# 03_CONNECTORS_AUDIO_CONTROL_INPUTS.net
KiCad netlist of a schematic drawn in Altium Designer
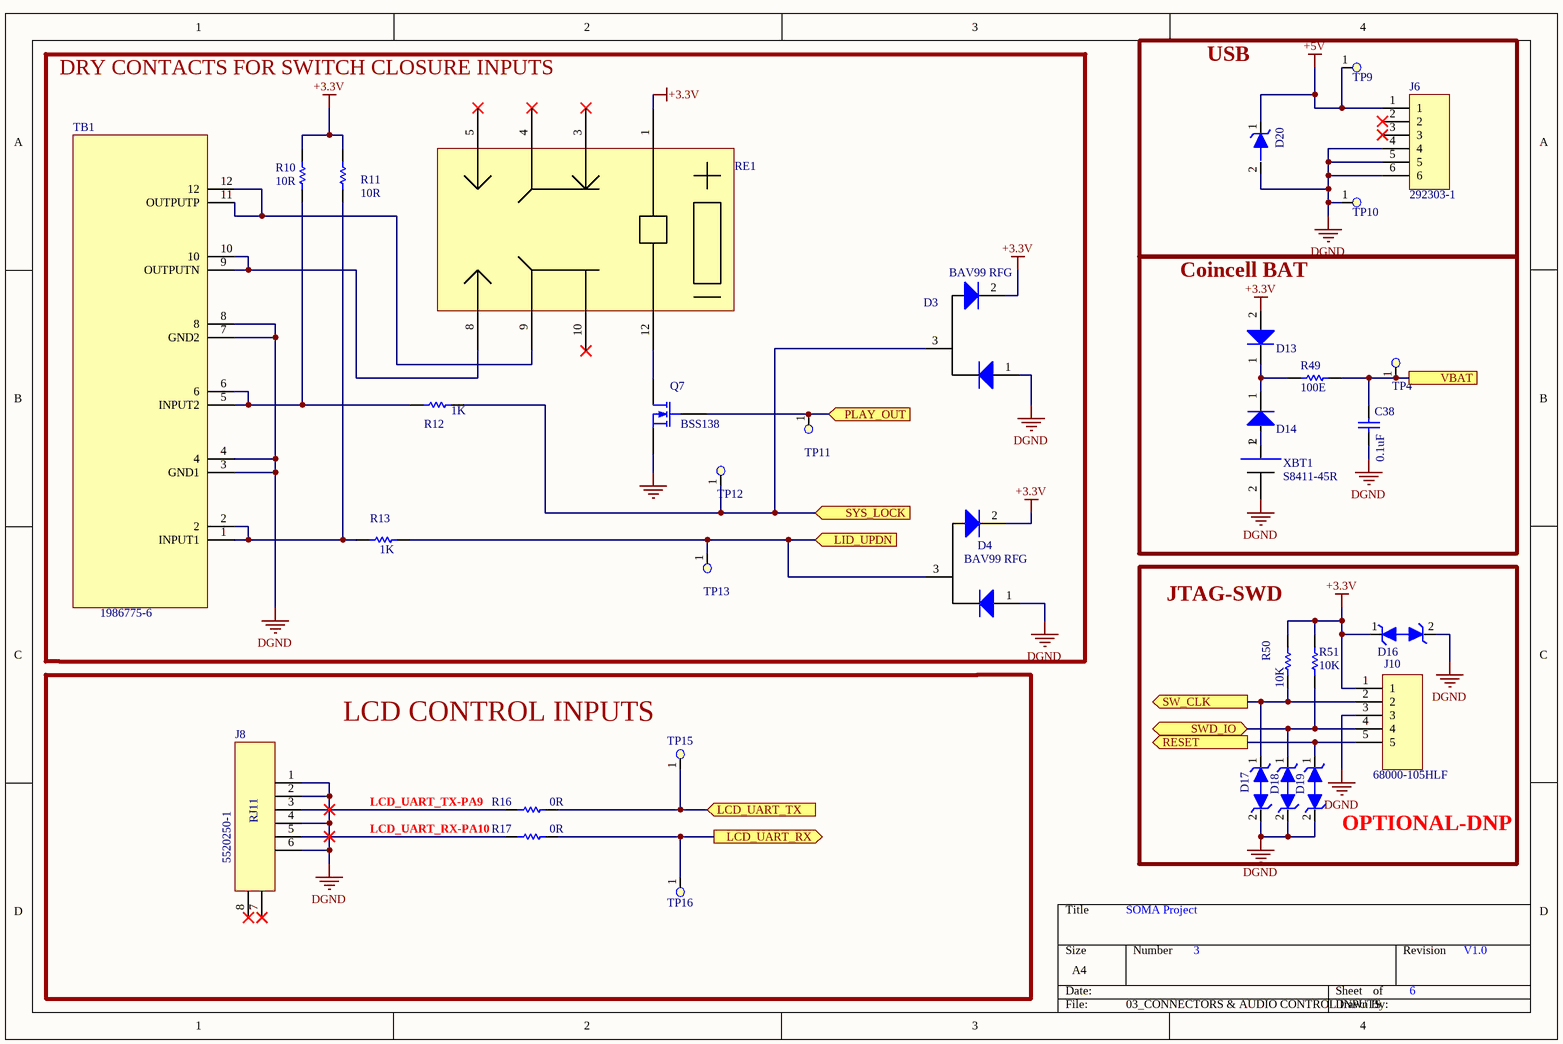
[diagram p0: 03_CONNECTORS & AUDIO CONTROL INPUTS.SchDoc]

(export (version "E")
  (design (tool "Eeschema 10.0.6"))
  (components
    (comp (ref "C38")
      (value "0.1uF")
      (footprint "C0603")
      (description "CAP CER 0.1UF 10V X7R 0603")
      (fields
        (field (name "MANUFACTURER") "Würth Elektronik")
        (field (name "DISTRIBUTOR PART NUMBER") "732-7939-1-ND")
      )
      (libsource (lib "SOMA_1") (part "CAP CER 0.1UF 10V X7R 0603"))
    )
    (comp (ref "D3")
      (value "BAV99 RFG")
      (footprint "SOT95P240X130-3N")
      (description "Diode Array 1 Pair Series Connection Standard 70V 200mA Surface Mount TO-236-3, SC-59, SOT-23-3")
      (fields
        (field (name "MANUFACTURER") "Taiwan Semiconductor Corporation")
        (field (name "DISTRIBUTOR PART NUMBER") "BAV99RFGTR-ND")
      )
      (libsource (lib "SOMA_15072021") (part "DIODE ARRAY GP 70V 200MA SOT23"))
    )
    (comp (ref "D4")
      (value "BAV99 RFG")
      (footprint "SOT95P240X130-3N")
      (description "Diode Array 1 Pair Series Connection Standard 70V 200mA Surface Mount TO-236-3, SC-59, SOT-23-3")
      (fields
        (field (name "MANUFACTURER") "Taiwan Semiconductor Corporation")
        (field (name "DISTRIBUTOR PART NUMBER") "BAV99RFGTR-ND")
      )
      (libsource (lib "SOMA_15072021") (part "DIODE ARRAY GP 70V 200MA SOT23"))
    )
    (comp (ref "D13")
      (value "DIODE SCHOTTKY 30V 200MA SOD123")
      (footprint "SOD3715X140N_2A")
      (fields
        (field (name "MANUFACTURER") "Diodes Incorporated")
        (field (name "MANUFACTURER PART NUMBER") "BAT43W-7-F")
        (field (name "DISTRIBUTOR PART NUMBER") "BAT43W-FDICT-ND")
      )
      (libsource (lib "SOMA_15072021") (part "DIODE SCHOTTKY 30V 200MA SOD123"))
    )
    (comp (ref "D14")
      (value "DIODE SCHOTTKY 30V 200MA SOD123")
      (footprint "SOD3715X140N_2A")
      (fields
        (field (name "MANUFACTURER") "Diodes Incorporated")
        (field (name "MANUFACTURER PART NUMBER") "BAT43W-7-F")
        (field (name "DISTRIBUTOR PART NUMBER") "BAT43W-FDICT-ND")
      )
      (libsource (lib "SOMA_15072021") (part "DIODE SCHOTTKY 30V 200MA SOD123"))
    )
    (comp (ref "D16")
      (value "TVS DIODE 3.3VWM 11.5VC SOD923")
      (footprint "SOD1006X40N_BI")
      (description "11.5V Clamp 2A (8/20µs) Ipp Tvs Diode Surface Mount SOD-923")
      (fields
        (field (name "MANUFACTURER PART NUMBER") "ESD9B3.3ST5G")
        (field (name "MANUFACTURER") "ON Semiconductor")
      )
      (libsource (lib "SOMA_15072021") (part "TVS DIODE 3.3VWM 11.5VC SOD923"))
    )
    (comp (ref "D17")
      (value "TVS DIODE 3.3VWM 11.5VC SOD923")
      (footprint "SOD1006X40N_BI")
      (description "11.5V Clamp 2A (8/20µs) Ipp Tvs Diode Surface Mount SOD-923")
      (fields
        (field (name "MANUFACTURER PART NUMBER") "ESD9B3.3ST5G")
        (field (name "MANUFACTURER") "ON Semiconductor")
      )
      (libsource (lib "SOMA_15072021") (part "TVS DIODE 3.3VWM 11.5VC SOD923"))
    )
    (comp (ref "D18")
      (value "TVS DIODE 3.3VWM 11.5VC SOD923")
      (footprint "SOD1006X40N_BI")
      (description "11.5V Clamp 2A (8/20µs) Ipp Tvs Diode Surface Mount SOD-923")
      (fields
        (field (name "MANUFACTURER PART NUMBER") "ESD9B3.3ST5G")
        (field (name "MANUFACTURER") "ON Semiconductor")
      )
      (libsource (lib "SOMA_15072021") (part "TVS DIODE 3.3VWM 11.5VC SOD923"))
    )
    (comp (ref "D19")
      (value "TVS DIODE 3.3VWM 11.5VC SOD923")
      (footprint "SOD1006X40N_BI")
      (description "11.5V Clamp 2A (8/20µs) Ipp Tvs Diode Surface Mount SOD-923")
      (fields
        (field (name "MANUFACTURER PART NUMBER") "ESD9B3.3ST5G")
        (field (name "MANUFACTURER") "ON Semiconductor")
      )
      (libsource (lib "SOMA_15072021") (part "TVS DIODE 3.3VWM 11.5VC SOD923"))
    )
    (comp (ref "D20")
      (value "TVS DIODE 5VWM 12VC SOD723")
      (footprint "SOD1460X65N_2A")
      (fields
        (field (name "MANUFACTURER PART NUMBER") "SP1003-01DTG")
        (field (name "MANUFACTURER") "Littelfuse Inc.")
        (field (name "DISTRIBUTOR PART NUMBER") "576-SP1003-01DTG")
      )
      (libsource (lib "SOMA_15072021") (part "SP1003-01DTG"))
    )
    (comp (ref "J6")
      (value "292303-1")
      (footprint "TE_292303-1")
      (description "CONN RCPT USB2.0 TYPEA 4POS R/A")
      (fields
        (field (name "DISTRIBUTOR PART NUMBER") "A31726-ND")
        (field (name "MANUFACTURER") "TE Connectivity AMP Connectors")
      )
      (libsource (lib "SOMA_15072021") (part "CONN RCPT USB2.0 TYPEA 4POS R/A"))
    )
    (comp (ref "J8")
      (value "CONN MOD JACK 6P2C R/A UNSHLD")
      (footprint "TE_5520250-1")
      (description "Jack Modular Connector 6p2c (RJ11) 90° Angle (Right) Unshielded Cat3")
      (fields
        (field (name "MANUFACTURER") "TE Connectivity AMP Connectors")
        (field (name "DISTRIBUTOR PART NUMBER") "A31404-ND")
        (field (name "MANUFACTURER PART NUMBER") "5520250-1")
      )
      (libsource (lib "SOMA_15072021") (part "CONN MOD JACK 6P2C R/A UNSHLD"))
    )
    (comp (ref "J10")
      (value "68000-105HLF")
      (footprint "BERG_1X5")
      (description "CONN HEADER VERT 5POS 2.54MM")
      (fields
        (field (name "DISTRIBUTOR PART NUMBER") "609-3462-ND")
        (field (name "MANUFACTURER") "Amphenol ICC (FCI)")
      )
      (libsource (lib "SOMA_15072021") (part "CONN HEADER VERT 5POS 2.54MM"))
    )
    (comp (ref "Q7")
      (value "BSS138")
      (footprint "SOT95P240X110-3N")
      (description "N-Channel 50V 220mA (Ta) 360mW (Ta) Surface Mount SOT-23-3")
      (fields
        (field (name "DISTRIBUTOR PART NUMBER") "BSS138CT-ND")
        (field (name "MANUFACTURER") "ON Semiconductor")
      )
      (libsource (lib "SOMA_15072021") (part "MOSFET N-CH 50V 220MA SOT23-3"))
    )
    (comp (ref "R10")
      (value "10R")
      (footprint "R0402")
      (description "10 Ohms ±5% 0.063W, 1/16W Chip Resistor 0402 (1005 Metric) Automotive AEC-Q200 Thick Film")
      (fields (field (name "TOLERANCE") "±5%") (field (name "MANUFACTURER") "Vishay Dale"))
      (libsource (lib "SOMA_15072021") (part "RES SMD 10 OHM 5% 1/16W 0402"))
    )
    (comp (ref "R11")
      (value "10R")
      (footprint "R0402")
      (description "10 Ohms ±5% 0.063W, 1/16W Chip Resistor 0402 (1005 Metric) Automotive AEC-Q200 Thick Film")
      (fields (field (name "TOLERANCE") "±5%") (field (name "MANUFACTURER") "Vishay Dale"))
      (libsource (lib "SOMA_15072021") (part "RES SMD 10 OHM 5% 1/16W 0402"))
    )
    (comp (ref "R12")
      (value "1K")
      (footprint "R0402")
      (description "RES SMD 1K OHM 1% 1/16W 0402")
      (fields (field (name "TOLERANCE") "±1%") (field (name "MANUFACTURER") "Yageo"))
      (libsource (lib "SOMA_15072021") (part "RES SMD 1K OHM 1% 1/16W 0402"))
    )
    (comp (ref "R13")
      (value "1K")
      (footprint "R0402")
      (description "RES SMD 1K OHM 1% 1/16W 0402")
      (fields (field (name "TOLERANCE") "±1%") (field (name "MANUFACTURER") "Yageo"))
      (libsource (lib "SOMA_15072021") (part "RES SMD 1K OHM 1% 1/16W 0402"))
    )
    (comp (ref "R16")
      (value "0R")
      (footprint "R0402")
      (description "0 Ohms Jumper 0.063W, 1/16W Chip Resistor 0402 (1005 Metric) Moisture Resistant Thick Film")
      (fields (field (name "MANUFACTURER") "Yageo") (field (name "DISTRIBUTOR PART NUMBER") "YAG1279TR-ND"))
      (libsource (lib "SOMA_1") (part "RES SMD 0 OHM JUMPER 1/16W 0402"))
    )
    (comp (ref "R17")
      (value "0R")
      (footprint "R0402")
      (description "0 Ohms Jumper 0.063W, 1/16W Chip Resistor 0402 (1005 Metric) Moisture Resistant Thick Film")
      (fields (field (name "MANUFACTURER") "Yageo") (field (name "DISTRIBUTOR PART NUMBER") "YAG1279TR-ND"))
      (libsource (lib "SOMA_1") (part "RES SMD 0 OHM JUMPER 1/16W 0402"))
    )
    (comp (ref "R49")
      (value "100E")
      (footprint "R0402")
      (description "100 Ohms ±1% 0.1W, 1/10W Chip Resistor 0402 (1005 Metric) Automotive AEC-Q200 Thick Film")
      (fields
        (field (name "MANUFACTURER") "Panasonic Electronic Components")
        (field (name "MANUFACTURER PART NUMBER") "ERJ-2RKF1000X")
      )
      (libsource (lib "SOMA_15072021") (part "RES SMD 100 OHM 1% 1/10W 0402"))
    )
    (comp (ref "R50")
      (value "10K")
      (footprint "R0402")
      (description "10 kOhms ±1% 0.1W, 1/10W Chip Resistor 0402 (1005 Metric) Automotive AEC-Q200 Thick Film")
      (fields
        (field (name "MANUFACTURER") "Panasonic Electronic Components")
        (field (name "DISTRIBUTOR PART NUMBER") "P10.0KLCT-ND")
      )
      (libsource (lib "Daughtercard_Library") (part "RES SMD 10K OHM 1% 1/10W 0402"))
    )
    (comp (ref "R51")
      (value "10K")
      (footprint "R0402")
      (description "10 kOhms ±1% 0.1W, 1/10W Chip Resistor 0402 (1005 Metric) Automotive AEC-Q200 Thick Film")
      (fields
        (field (name "MANUFACTURER") "Panasonic Electronic Components")
        (field (name "DISTRIBUTOR PART NUMBER") "P10.0KLCT-ND")
      )
      (libsource (lib "Daughtercard_Library") (part "RES SMD 10K OHM 1% 1/10W 0402"))
    )
    (comp (ref "RE1")
      (value "RELAY GEN PURPOSE DPDT 1A 3VDC")
      (footprint "RELAY_TXS2SA-3V")
      (description "General Purpose Relay DPDT (2 Form C) Surface Mount")
      (fields
        (field (name "DISTRIBUTOR PART NUMBER") "255-2341-5-ND")
        (field (name "MANUFACTURER") "Panasonic Electric Works")
      )
      (libsource (lib "SOMA_15072021") (part "RELAY GEN PURPOSE DPDT 1A 3VDC"))
    )
    (comp (ref "TB1")
      (value "TERM BLK 6P SIDE ENT 5.08MM PCB")
      (footprint "TE_1986775-6")
      (description "6 Position Wire to Board Terminal Block Horizontal with Board 0.200\" (5.08mm) Through Hole")
      (fields
        (field (name "MANUFACTURER") "TE Connectivity AMP Connectors")
        (field (name "MANUFACTURER PART NUMBER") "1986775-6")
        (field (name "DISTRIBUTOR PART NUMBER") "A120496-ND")
      )
      (libsource (lib "SOMA_15072021") (part "TERM BLK 6P SIDE ENT 5.08MM PCB"))
    )
    (comp (ref "TP4")
      (value "Test Point,1.6mm Diameter,SMD")
      (footprint "TP_63C")
      (libsource (lib "SOMA_1") (part "Test Point,1.6mm Diameter,SMD"))
    )
    (comp (ref "TP9")
      (value "Test Point,1.6mm Diameter,SMD")
      (footprint "TP_63C")
      (libsource (lib "SOMA_1") (part "Test Point,1.6mm Diameter,SMD"))
    )
    (comp (ref "TP10")
      (value "Test Point,1.6mm Diameter,SMD")
      (footprint "TP_63C")
      (libsource (lib "SOMA_1") (part "Test Point,1.6mm Diameter,SMD"))
    )
    (comp (ref "TP11")
      (value "Test Point,1.6mm Diameter,SMD")
      (footprint "TP_63C")
      (libsource (lib "SOMA_1") (part "Test Point,1.6mm Diameter,SMD"))
    )
    (comp (ref "TP12")
      (value "Test Point,1.6mm Diameter,SMD")
      (footprint "TP_63C")
      (libsource (lib "SOMA_1") (part "Test Point,1.6mm Diameter,SMD"))
    )
    (comp (ref "TP13")
      (value "Test Point,1.6mm Diameter,SMD")
      (footprint "TP_63C")
      (libsource (lib "SOMA_1") (part "Test Point,1.6mm Diameter,SMD"))
    )
    (comp (ref "TP15")
      (value "Test Point,1.6mm Diameter,SMD")
      (footprint "TP_63C")
      (libsource (lib "SOMA_1") (part "Test Point,1.6mm Diameter,SMD"))
    )
    (comp (ref "TP16")
      (value "Test Point,1.6mm Diameter,SMD")
      (footprint "TP_63C")
      (libsource (lib "SOMA_1") (part "Test Point,1.6mm Diameter,SMD"))
    )
    (comp (ref "XBT1")
      (value "BATTERY HOLDER COIN 12MM SMD")
      (footprint "HLDR_S8411-45R")
      (fields
        (field (name "MANUFACTURER") "Harwin Inc.")
        (field (name "DISTRIBUTOR PART NUMBER") "952-1745-1-ND")
        (field (name "MANUFACTURER PART NUMBER") "S8411-45R")
      )
      (libsource (lib "SOMA_15072021") (part "BATTERY HOLDER COIN 12MM SMD"))
    )
  )
  (nets
    (net (code "1") (name "+3.3V") (class "Default")
      (node (ref "D13") (pin "2") (pinfunction "A_2") (pintype "passive"))
      (node (ref "D16") (pin "1") (pinfunction "K_1") (pintype "passive"))
      (node (ref "D3") (pin "2") (pinfunction "K_2") (pintype "passive"))
      (node (ref "D4") (pin "2") (pinfunction "K_2") (pintype "passive"))
      (node (ref "J10") (pin "1") (pinfunction "1_1") (pintype "passive"))
      (node (ref "R10") (pin "2") (pinfunction "2_2") (pintype "passive"))
      (node (ref "R11") (pin "2") (pinfunction "2_2") (pintype "passive"))
      (node (ref "R50") (pin "2") (pinfunction "2_2") (pintype "passive"))
      (node (ref "R51") (pin "2") (pinfunction "2_2") (pintype "passive"))
      (node (ref "RE1") (pin "1") (pinfunction "1_1") (pintype "passive"))
    )
    (net (code "2") (name "+5V") (class "Default")
      (node (ref "D20") (pin "1") (pinfunction "K_1") (pintype "passive"))
      (node (ref "J6") (pin "1") (pinfunction "1_1") (pintype "passive"))
      (node (ref "TP9") (pin "1") (pinfunction "0_1") (pintype "passive"))
    )
    (net (code "3") (name "/LCD_UART_RX") (class "Default")
      (node (ref "R17") (pin "2") (pinfunction "2_2") (pintype "passive"))
      (node (ref "TP16") (pin "1") (pinfunction "0_1") (pintype "passive"))
    )
    (net (code "4") (name "/LCD_UART_RX-PA10") (class "Default")
      (node (ref "J8") (pin "5") (pinfunction "5_5") (pintype "passive"))
      (node (ref "R17") (pin "1") (pinfunction "1_1") (pintype "passive"))
    )
    (net (code "5") (name "/LCD_UART_TX") (class "Default")
      (node (ref "R16") (pin "2") (pinfunction "2_2") (pintype "passive"))
      (node (ref "TP15") (pin "1") (pinfunction "0_1") (pintype "passive"))
    )
    (net (code "6") (name "/LCD_UART_TX-PA9") (class "Default")
      (node (ref "J8") (pin "3") (pinfunction "3_3") (pintype "passive"))
      (node (ref "R16") (pin "1") (pinfunction "1_1") (pintype "passive"))
    )
    (net (code "7") (name "/LID_UPDN") (class "Default")
      (node (ref "D4") (pin "3") (pinfunction "AK_3") (pintype "passive"))
      (node (ref "R13") (pin "2") (pinfunction "2_2") (pintype "passive"))
      (node (ref "TP13") (pin "1") (pinfunction "0_1") (pintype "passive"))
    )
    (net (code "8") (name "/PLAY_OUT") (class "Default")
      (node (ref "Q7") (pin "1") (pinfunction "G_1") (pintype "passive"))
      (node (ref "TP11") (pin "1") (pinfunction "0_1") (pintype "passive"))
    )
    (net (code "9") (name "/RESET") (class "Default")
      (node (ref "D19") (pin "1") (pinfunction "K_1") (pintype "passive"))
      (node (ref "J10") (pin "5") (pinfunction "5_5") (pintype "passive"))
    )
    (net (code "10") (name "/SWD_IO") (class "Default")
      (node (ref "D18") (pin "1") (pinfunction "K_1") (pintype "passive"))
      (node (ref "J10") (pin "4") (pinfunction "4_4") (pintype "passive"))
      (node (ref "R51") (pin "1") (pinfunction "1_1") (pintype "passive"))
    )
    (net (code "11") (name "/SW_CLK") (class "Default")
      (node (ref "D17") (pin "1") (pinfunction "K_1") (pintype "passive"))
      (node (ref "J10") (pin "2") (pinfunction "2_2") (pintype "passive"))
      (node (ref "R50") (pin "1") (pinfunction "1_1") (pintype "passive"))
    )
    (net (code "12") (name "/SYS_LOCK") (class "Default")
      (node (ref "D3") (pin "3") (pinfunction "AK_3") (pintype "passive"))
      (node (ref "R12") (pin "2") (pinfunction "2_2") (pintype "passive"))
      (node (ref "TP12") (pin "1") (pinfunction "0_1") (pintype "passive"))
    )
    (net (code "13") (name "/VBAT") (class "Default")
      (node (ref "C38") (pin "2") (pinfunction "2_2") (pintype "passive"))
      (node (ref "R49") (pin "2") (pinfunction "2_2") (pintype "passive"))
      (node (ref "TP4") (pin "1") (pinfunction "0_1") (pintype "passive"))
    )
    (net (code "14") (name "DGND") (class "Default")
      (node (ref "C38") (pin "1") (pinfunction "1_1") (pintype "passive"))
      (node (ref "D16") (pin "2") (pinfunction "A_2") (pintype "passive"))
      (node (ref "D17") (pin "2") (pinfunction "A_2") (pintype "passive"))
      (node (ref "D18") (pin "2") (pinfunction "A_2") (pintype "passive"))
      (node (ref "D19") (pin "2") (pinfunction "A_2") (pintype "passive"))
      (node (ref "D20") (pin "2") (pinfunction "A_2") (pintype "passive"))
      (node (ref "D3") (pin "1") (pinfunction "A_1") (pintype "passive"))
      (node (ref "D4") (pin "1") (pinfunction "A_1") (pintype "passive"))
      (node (ref "J10") (pin "3") (pinfunction "3_3") (pintype "passive"))
      (node (ref "J6") (pin "4") (pinfunction "4_4") (pintype "passive"))
      (node (ref "J6") (pin "5") (pinfunction "5_5") (pintype "passive"))
      (node (ref "J6") (pin "6") (pinfunction "6_6") (pintype "passive"))
      (node (ref "J8") (pin "1") (pinfunction "1_1") (pintype "passive"))
      (node (ref "J8") (pin "2") (pinfunction "2_2") (pintype "passive"))
      (node (ref "J8") (pin "4") (pinfunction "4_4") (pintype "passive"))
      (node (ref "J8") (pin "6") (pinfunction "6_6") (pintype "passive"))
      (node (ref "TB1") (pin "3") (pinfunction "GND1_3") (pintype "passive"))
      (node (ref "TB1") (pin "4") (pinfunction "4_4") (pintype "passive"))
      (node (ref "TB1") (pin "7") (pinfunction "GND2_7") (pintype "passive"))
      (node (ref "TB1") (pin "8") (pinfunction "8_8") (pintype "passive"))
      (node (ref "TP10") (pin "1") (pinfunction "0_1") (pintype "passive"))
      (node (ref "XBT1") (pin "2") (pinfunction "-_2") (pintype "passive"))
    )
    (net (code "15") (name "GND") (class "Default")
      (node (ref "Q7") (pin "2") (pinfunction "S_2") (pintype "passive"))
    )
    (net (code "16") (name "Net-(D13-K)") (class "Default")
      (node (ref "D13") (pin "1") (pinfunction "K_1") (pintype "passive"))
      (node (ref "D14") (pin "1") (pinfunction "K_1") (pintype "passive"))
      (node (ref "R49") (pin "1") (pinfunction "1_1") (pintype "passive"))
    )
    (net (code "17") (name "Net-(D14-A)") (class "Default")
      (node (ref "D14") (pin "2") (pinfunction "A_2") (pintype "passive"))
      (node (ref "XBT1") (pin "1") (pinfunction "+_1") (pintype "passive"))
    )
    (net (code "18") (name "Net-(Q7-D)") (class "Default")
      (node (ref "Q7") (pin "3") (pinfunction "D_3") (pintype "passive"))
      (node (ref "RE1") (pin "12") (pinfunction "12_12") (pintype "passive"))
    )
    (net (code "19") (name "Net-(TB1-INPUT1)") (class "Default")
      (node (ref "R11") (pin "1") (pinfunction "1_1") (pintype "passive"))
      (node (ref "R13") (pin "1") (pinfunction "1_1") (pintype "passive"))
      (node (ref "TB1") (pin "1") (pinfunction "INPUT1_1") (pintype "passive"))
      (node (ref "TB1") (pin "2") (pinfunction "2_2") (pintype "passive"))
    )
    (net (code "20") (name "Net-(TB1-INPUT2)") (class "Default")
      (node (ref "R10") (pin "1") (pinfunction "1_1") (pintype "passive"))
      (node (ref "R12") (pin "1") (pinfunction "1_1") (pintype "passive"))
      (node (ref "TB1") (pin "5") (pinfunction "INPUT2_5") (pintype "passive"))
      (node (ref "TB1") (pin "6") (pinfunction "6_6") (pintype "passive"))
    )
    (net (code "21") (name "Net-(TB1-OUTPUTN)") (class "Default")
      (node (ref "RE1") (pin "8") (pinfunction "8_8") (pintype "passive"))
      (node (ref "TB1") (pin "10") (pinfunction "10_10") (pintype "passive"))
      (node (ref "TB1") (pin "9") (pinfunction "OUTPUTN_9") (pintype "passive"))
    )
    (net (code "22") (name "Net-(TB1-OUTPUTP)") (class "Default")
      (node (ref "RE1") (pin "9") (pinfunction "9_9") (pintype "passive"))
      (node (ref "TB1") (pin "11") (pinfunction "OUTPUTP_11") (pintype "passive"))
      (node (ref "TB1") (pin "12") (pinfunction "12_12") (pintype "passive"))
    )
    (net (code "23") (name "unconnected-(J6-Pad2)") (class "Default")
      (node (ref "J6") (pin "2") (pinfunction "2_2") (pintype "passive+no_connect"))
    )
    (net (code "24") (name "unconnected-(J6-Pad3)") (class "Default")
      (node (ref "J6") (pin "3") (pinfunction "3_3") (pintype "passive+no_connect"))
    )
    (net (code "25") (name "unconnected-(J8-Pad7)") (class "Default")
      (node (ref "J8") (pin "7") (pinfunction "7_7") (pintype "passive+no_connect"))
    )
    (net (code "26") (name "unconnected-(J8-Pad8)") (class "Default")
      (node (ref "J8") (pin "8") (pinfunction "8_8") (pintype "passive+no_connect"))
    )
    (net (code "27") (name "unconnected-(RE1-Pad3)") (class "Default")
      (node (ref "RE1") (pin "3") (pinfunction "3_3") (pintype "passive+no_connect"))
    )
    (net (code "28") (name "unconnected-(RE1-Pad4)") (class "Default")
      (node (ref "RE1") (pin "4") (pinfunction "4_4") (pintype "passive+no_connect"))
    )
    (net (code "29") (name "unconnected-(RE1-Pad5)") (class "Default")
      (node (ref "RE1") (pin "5") (pinfunction "5_5") (pintype "passive+no_connect"))
    )
    (net (code "30") (name "unconnected-(RE1-Pad10)") (class "Default")
      (node (ref "RE1") (pin "10") (pinfunction "10_10") (pintype "passive+no_connect"))
    )
  )
)
